# LED_STRIP_DRIVER.net
KiCad netlist of a schematic drawn in Altium Designer
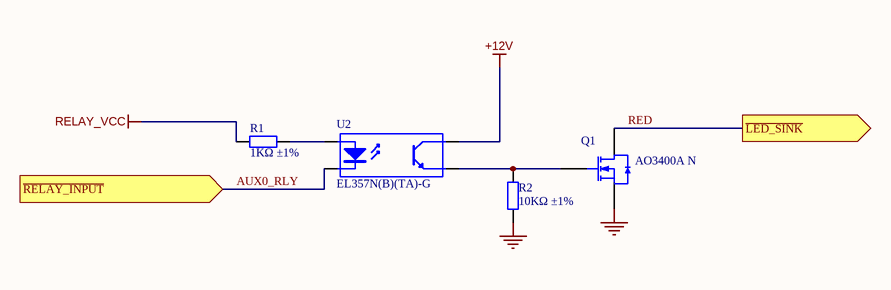
[diagram p0: LED_STRIP_DRIVER.SchDoc]

(export (version "E")
  (design (tool "Eeschema 10.0.6"))
  (components
    (comp (ref "Q1")
      (value "AO3400A N")
      (footprint "SOT-23-3L")
      (description "MOS(场效应管)")
      (libsource (lib "PrintNC_GRBLHAL_Breakout") (part "AO3400A N道沟 X0YV1T SOT-23"))
    )
    (comp (ref "R1")
      (value "1KΩ ±1%")
      (footprint "0402_R")
      (description "Chip resistor")
      (fields (field (name "MANUFACTURER") "Uniroyal Elec") (field (name "PARTNUMBER") "0402WGF1001TCE"))
      (libsource (lib "RES") (part "0402 1K (1001) 1%"))
    )
    (comp (ref "R2")
      (value "10KΩ ±1%")
      (footprint "0402_R")
      (description "Chip resistor")
      (fields (field (name "MANUFACTURER") "Uniroyal Elec") (field (name "PARTNUMBER") "0402WGF1002TCE"))
      (libsource (lib "PrintNC_GRBLHAL_Breakout") (part "0402 10K (1002) 1%"))
    )
    (comp (ref "U2")
      (value "EL357N(B)(TA)-G")
      (footprint "SOP-4_P2.54")
      (description "Optocoupler SOP-4, EL357N(B)(TA)-G, Everlight Electronics")
      (libsource (lib "PrintNC_GRBLHAL_Breakout") (part "EL357N(B)(TA)-G_[C6649]"))
    )
  )
  (nets
    (net (code "1") (name "+12V") (class "Default")
      (node (ref "U2") (pin "4") (pinfunction "C_4") (pintype "passive"))
    )
    (net (code "2") (name "/AUX0_RLY") (class "Default")
      (node (ref "U2") (pin "2") (pinfunction "K_2") (pintype "passive"))
    )
    (net (code "3") (name "/RED") (class "Default")
      (node (ref "Q1") (pin "3") (pinfunction "D_3") (pintype "passive"))
    )
    (net (code "4") (name "GND") (class "Default")
      (node (ref "Q1") (pin "2") (pinfunction "S_2") (pintype "passive"))
      (node (ref "R2") (pin "1") (pinfunction "1_1") (pintype "passive"))
    )
    (net (code "5") (name "Net-(Q1-G)") (class "Default")
      (node (ref "Q1") (pin "1") (pinfunction "G_1") (pintype "passive"))
      (node (ref "R2") (pin "2") (pinfunction "2_2") (pintype "passive"))
      (node (ref "U2") (pin "3") (pinfunction "E_3") (pintype "passive"))
    )
    (net (code "6") (name "Net-(U2-A)") (class "Default")
      (node (ref "R1") (pin "2") (pinfunction "2_2") (pintype "passive"))
      (node (ref "U2") (pin "1") (pinfunction "A_1") (pintype "passive"))
    )
    (net (code "7") (name "RELAY_VCC") (class "Default")
      (node (ref "R1") (pin "1") (pinfunction "1_1") (pintype "passive"))
    )
  )
)
